# DDR3L_16bits.net
KiCad netlist of a schematic drawn in Altium Designer
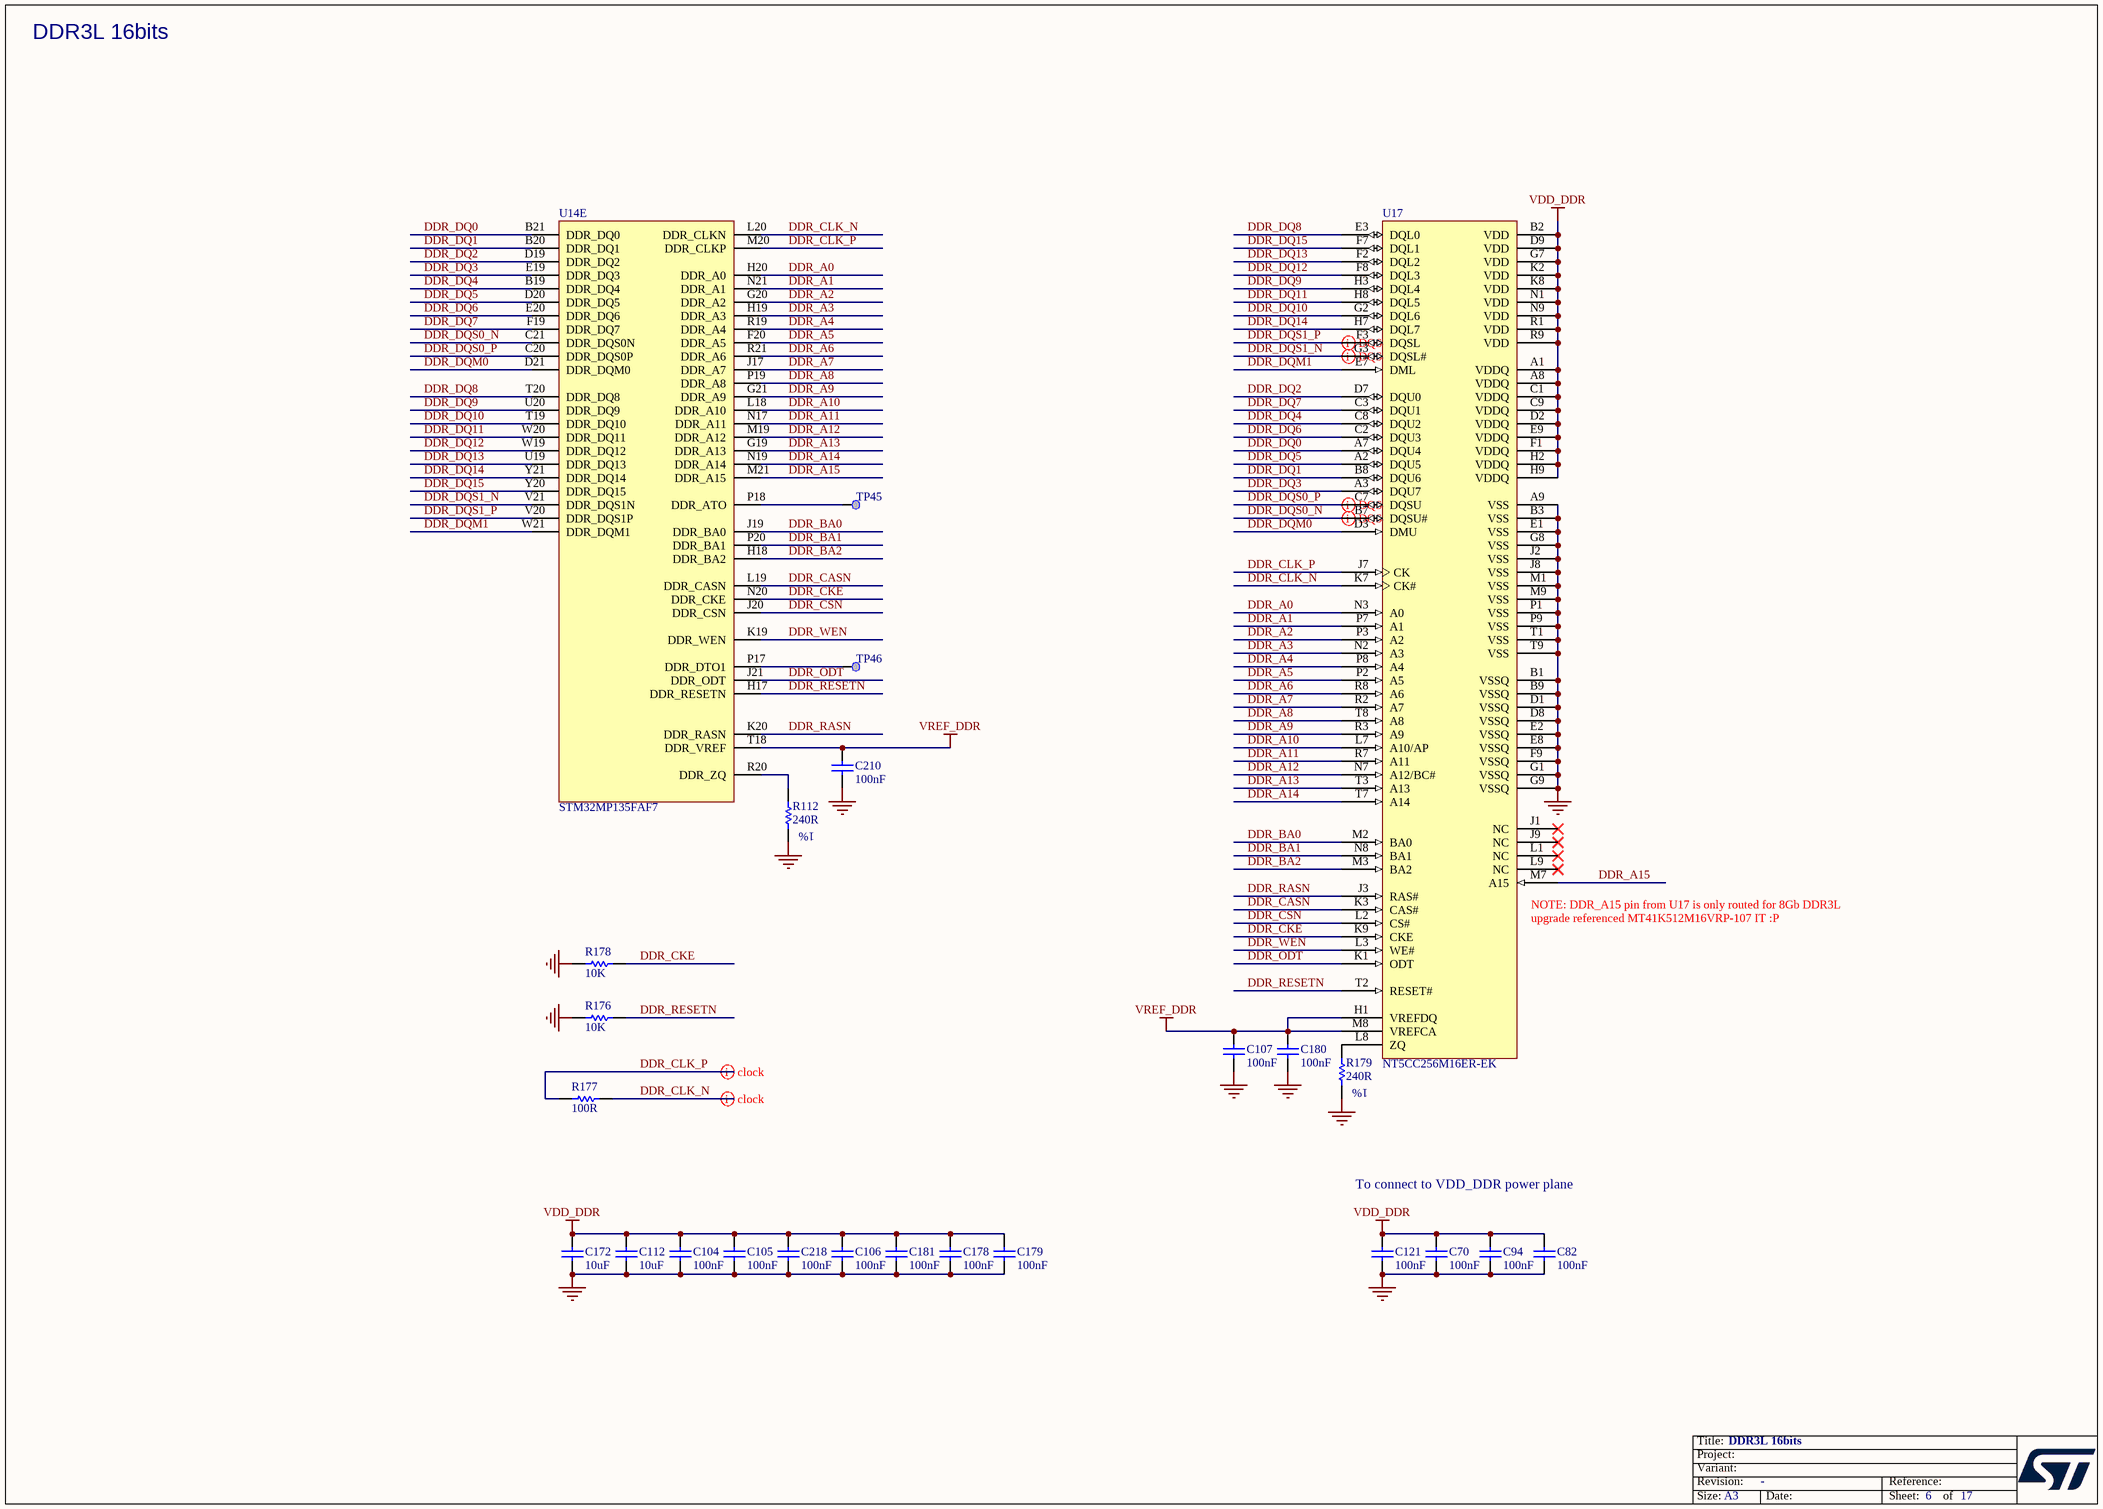
[diagram p0: DDR3L_16bits.SchDoc]

(export (version "E")
  (design (tool "Eeschema 10.0.6"))
  (components
    (comp (ref "C70")
      (value "100nF")
      (footprint "C0402")
      (description "Capacitor, MLCC, 100nF, 16V, X7R, +/-10%, 0402, T=0.5mm")
      (fields (field (name "INTERNAL_PART_NUMBER") "MCD-00006") (field (name "MANUFACTURER") "YAGEO"))
      (libsource (lib "MCD_PARTS_database") (part "Capacitor"))
    )
    (comp (ref "C82")
      (value "100nF")
      (footprint "C0402")
      (description "Capacitor, MLCC, 100nF, 16V, X7R, +/-10%, 0402, T=0.5mm")
      (fields (field (name "INTERNAL_PART_NUMBER") "MCD-00006") (field (name "MANUFACTURER") "YAGEO"))
      (libsource (lib "MCD_PARTS_database") (part "Capacitor"))
    )
    (comp (ref "C94")
      (value "100nF")
      (footprint "C0402")
      (description "Capacitor, MLCC, 100nF, 16V, X7R, +/-10%, 0402, T=0.5mm")
      (fields (field (name "INTERNAL_PART_NUMBER") "MCD-00006") (field (name "MANUFACTURER") "YAGEO"))
      (libsource (lib "MCD_PARTS_database") (part "Capacitor"))
    )
    (comp (ref "C104")
      (value "100nF")
      (footprint "C0402")
      (description "Capacitor, MLCC, 100nF, 16V, X7R, +/-10%, 0402, T=0.5mm")
      (fields (field (name "INTERNAL_PART_NUMBER") "MCD-00006") (field (name "MANUFACTURER") "YAGEO"))
      (libsource (lib "MCD_PARTS_database") (part "Capacitor"))
    )
    (comp (ref "C105")
      (value "100nF")
      (footprint "C0402")
      (description "Capacitor, MLCC, 100nF, 16V, X7R, +/-10%, 0402, T=0.5mm")
      (fields (field (name "INTERNAL_PART_NUMBER") "MCD-00006") (field (name "MANUFACTURER") "YAGEO"))
      (libsource (lib "MCD_PARTS_database") (part "Capacitor"))
    )
    (comp (ref "C106")
      (value "100nF")
      (footprint "C0402")
      (description "Capacitor, MLCC, 100nF, 16V, X7R, +/-10%, 0402, T=0.5mm")
      (fields (field (name "INTERNAL_PART_NUMBER") "MCD-00006") (field (name "MANUFACTURER") "YAGEO"))
      (libsource (lib "MCD_PARTS_database") (part "Capacitor"))
    )
    (comp (ref "C107")
      (value "100nF")
      (footprint "C0402")
      (description "Capacitor, MLCC, 100nF, 16V, X7R, +/-10%, 0402, T=0.5mm")
      (fields
        (field (name "INTERNAL_PART_NUMBER") "MCD-00006")
        (field (name "MANUFACTURER_PART_NUMBER") "CC0402KRX7R7BB104")
      )
      (libsource (lib "MCD_PARTS_database") (part "Capacitor"))
    )
    (comp (ref "C112")
      (value "10uF")
      (footprint "C0603")
      (description "Capacitor, MLCC, 10uF, 10V, X5R, +/-10%, 0603, T=0.8mm")
      (fields
        (field (name "INTERNAL_PART_NUMBER") "MCD-00099")
        (field (name "MANUFACTURER_PART_NUMBER") "GRM188R61A106KE69D")
      )
      (libsource (lib "MCD_PARTS_database") (part "Capacitor"))
    )
    (comp (ref "C121")
      (value "100nF")
      (footprint "C0402")
      (description "Capacitor, MLCC, 100nF, 16V, X7R, +/-10%, 0402, T=0.5mm")
      (fields (field (name "INTERNAL_PART_NUMBER") "MCD-00006") (field (name "MANUFACTURER") "YAGEO"))
      (libsource (lib "MCD_PARTS_database") (part "Capacitor"))
    )
    (comp (ref "C172")
      (value "10uF")
      (footprint "C0603")
      (description "Capacitor, MLCC, 10uF, 10V, X5R, +/-10%, 0603, T=0.8mm")
      (fields
        (field (name "INTERNAL_PART_NUMBER") "MCD-00099")
        (field (name "MANUFACTURER_PART_NUMBER") "GRM188R61A106KE69D")
      )
      (libsource (lib "MCD_PARTS_database") (part "Capacitor"))
    )
    (comp (ref "C178")
      (value "100nF")
      (footprint "C0402")
      (description "Capacitor, MLCC, 100nF, 16V, X7R, +/-10%, 0402, T=0.5mm")
      (fields (field (name "INTERNAL_PART_NUMBER") "MCD-00006") (field (name "MANUFACTURER") "YAGEO"))
      (libsource (lib "MCD_PARTS_database") (part "Capacitor"))
    )
    (comp (ref "C179")
      (value "100nF")
      (footprint "C0402")
      (description "Capacitor, MLCC, 100nF, 16V, X7R, +/-10%, 0402, T=0.5mm")
      (fields (field (name "INTERNAL_PART_NUMBER") "MCD-00006") (field (name "MANUFACTURER") "YAGEO"))
      (libsource (lib "MCD_PARTS_database") (part "Capacitor"))
    )
    (comp (ref "C180")
      (value "100nF")
      (footprint "C0402")
      (description "Capacitor, MLCC, 100nF, 16V, X7R, +/-10%, 0402, T=0.5mm")
      (fields
        (field (name "INTERNAL_PART_NUMBER") "MCD-00006")
        (field (name "MANUFACTURER_PART_NUMBER") "CC0402KRX7R7BB104")
      )
      (libsource (lib "MCD_PARTS_database") (part "Capacitor"))
    )
    (comp (ref "C181")
      (value "100nF")
      (footprint "C0402")
      (description "Capacitor, MLCC, 100nF, 16V, X7R, +/-10%, 0402, T=0.5mm")
      (fields (field (name "INTERNAL_PART_NUMBER") "MCD-00006") (field (name "MANUFACTURER") "YAGEO"))
      (libsource (lib "MCD_PARTS_database") (part "Capacitor"))
    )
    (comp (ref "C210")
      (value "100nF")
      (footprint "C0402")
      (description "Capacitor, MLCC, 100nF, 16V, X7R, +/-10%, 0402, T=0.5mm")
      (fields (field (name "INTERNAL_PART_NUMBER") "MCD-00006") (field (name "MANUFACTURER") "YAGEO"))
      (libsource (lib "MCD_PARTS_database") (part "Capacitor"))
    )
    (comp (ref "C218")
      (value "100nF")
      (footprint "C0402")
      (description "Capacitor, MLCC, 100nF, 16V, X7R, +/-10%, 0402, T=0.5mm")
      (fields (field (name "INTERNAL_PART_NUMBER") "MCD-00006") (field (name "MANUFACTURER") "YAGEO"))
      (libsource (lib "MCD_PARTS_database") (part "Capacitor"))
    )
    (comp (ref "R112")
      (value "240R")
      (footprint "R0402")
      (description "Resistor, 240R, 0402, +/-1%, 1/16W")
      (fields (field (name "INTERNAL_PART_NUMBER") "MCD-00120") (field (name "MANUFACTURER") "YAGEO"))
      (libsource (lib "MCD_PARTS_database") (part "Resistor"))
    )
    (comp (ref "R176")
      (value "10K")
      (footprint "R0402")
      (description "Resistor, 10K, 0402, +/-1%, 1/16W")
      (fields
        (field (name "INTERNAL_PART_NUMBER") "MCD-00053")
        (field (name "MANUFACTURER_PART_NUMBER") "RC0402FR-0710KL")
      )
      (libsource (lib "MCD_PARTS_database") (part "Resistor"))
    )
    (comp (ref "R177")
      (value "100R")
      (footprint "R0402")
      (description "Resistor, 100R, 0402, +/- 1%, 1/16W")
      (fields
        (field (name "INTERNAL_PART_NUMBER") "MCD-00067")
        (field (name "MANUFACTURER_PART_NUMBER") "RC0402FR-07100RL")
      )
      (libsource (lib "MCD_PARTS_database") (part "Resistor"))
    )
    (comp (ref "R178")
      (value "10K")
      (footprint "R0402")
      (description "Resistor, 10K, 0402, +/-1%, 1/16W")
      (fields
        (field (name "INTERNAL_PART_NUMBER") "MCD-00053")
        (field (name "MANUFACTURER_PART_NUMBER") "RC0402FR-0710KL")
      )
      (libsource (lib "MCD_PARTS_database") (part "Resistor"))
    )
    (comp (ref "R179")
      (value "240R")
      (footprint "R0402")
      (description "Resistor, 240R, 0402, +/-1%, 1/16W")
      (fields
        (field (name "INTERNAL_PART_NUMBER") "MCD-00120")
        (field (name "MANUFACTURER_PART_NUMBER") "RC0402FR-07240RL")
      )
      (libsource (lib "MCD_PARTS_database") (part "Resistor"))
    )
    (comp (ref "TP45")
      (value "Test Point")
      (footprint "TP_SMD_1MM")
      (description "Test Point 1mm")
      (fields (field (name "INTERNAL_PART_NUMBER") "MCD-00074"))
      (libsource (lib "MCD_PARTS_database") (part "Test Point"))
    )
    (comp (ref "TP46")
      (value "Test Point")
      (footprint "TP_SMD_1MM")
      (description "Test Point 1mm")
      (fields (field (name "INTERNAL_PART_NUMBER") "MCD-00074"))
      (libsource (lib "MCD_PARTS_database") (part "Test Point"))
    )
    (comp (ref "U14")
      (value "STM32MP135FAF7")
      (footprint "ICC_TFBGA320_11X11_STM32MP135FA7_P050_H1P20")
      (fields
        (field (name "INTERNAL_PART_NUMBER") "MCD-02251")
        (field (name "MANUFACTURER") "STMICROELECTRONICS")
      )
      (libsource (lib "MCD_PARTS_database") (part "STM32MP135FAF7"))
    )
    (comp (ref "U17")
      (value "NT5CC256M16ER-EK")
      (footprint "ICC_VFBGA96_9x13_P080")
      (description "Memory,DDR3L,4Gb,256Mbx16,933Mhz,1V35,TFBGA")
      (fields (field (name "INTERNAL_PART_NUMBER") "MCD-01811") (field (name "MANUFACTURER") "NANYA"))
      (libsource (lib "MCD_PARTS_database") (part "NT5CC256M16ER-EK"))
    )
  )
  (nets
    (net (code "1") (name "/DDR_A0") (class "Default")
      (node (ref "U14") (pin "H20") (pinfunction "DDR_A0_H20") (pintype "passive"))
      (node (ref "U17") (pin "N3") (pinfunction "A0_N3") (pintype "input"))
    )
    (net (code "2") (name "/DDR_A1") (class "Default")
      (node (ref "U14") (pin "N21") (pinfunction "DDR_A1_N21") (pintype "passive"))
      (node (ref "U17") (pin "P7") (pinfunction "A1_P7") (pintype "input"))
    )
    (net (code "3") (name "/DDR_A2") (class "Default")
      (node (ref "U14") (pin "G20") (pinfunction "DDR_A2_G20") (pintype "passive"))
      (node (ref "U17") (pin "P3") (pinfunction "A2_P3") (pintype "input"))
    )
    (net (code "4") (name "/DDR_A3") (class "Default")
      (node (ref "U14") (pin "H19") (pinfunction "DDR_A3_H19") (pintype "passive"))
      (node (ref "U17") (pin "N2") (pinfunction "A3_N2") (pintype "input"))
    )
    (net (code "5") (name "/DDR_A4") (class "Default")
      (node (ref "U14") (pin "R19") (pinfunction "DDR_A4_R19") (pintype "passive"))
      (node (ref "U17") (pin "P8") (pinfunction "A4_P8") (pintype "input"))
    )
    (net (code "6") (name "/DDR_A5") (class "Default")
      (node (ref "U14") (pin "F20") (pinfunction "DDR_A5_F20") (pintype "passive"))
      (node (ref "U17") (pin "P2") (pinfunction "A5_P2") (pintype "input"))
    )
    (net (code "7") (name "/DDR_A6") (class "Default")
      (node (ref "U14") (pin "R21") (pinfunction "DDR_A6_R21") (pintype "passive"))
      (node (ref "U17") (pin "R8") (pinfunction "A6_R8") (pintype "input"))
    )
    (net (code "8") (name "/DDR_A7") (class "Default")
      (node (ref "U14") (pin "J17") (pinfunction "DDR_A7_J17") (pintype "passive"))
      (node (ref "U17") (pin "R2") (pinfunction "A7_R2") (pintype "input"))
    )
    (net (code "9") (name "/DDR_A8") (class "Default")
      (node (ref "U14") (pin "P19") (pinfunction "DDR_A8_P19") (pintype "passive"))
      (node (ref "U17") (pin "T8") (pinfunction "A8_T8") (pintype "input"))
    )
    (net (code "10") (name "/DDR_A9") (class "Default")
      (node (ref "U14") (pin "G21") (pinfunction "DDR_A9_G21") (pintype "passive"))
      (node (ref "U17") (pin "R3") (pinfunction "A9_R3") (pintype "input"))
    )
    (net (code "11") (name "/DDR_A10") (class "Default")
      (node (ref "U14") (pin "L18") (pinfunction "DDR_A10_L18") (pintype "passive"))
      (node (ref "U17") (pin "L7") (pinfunction "A10/AP_L7") (pintype "input"))
    )
    (net (code "12") (name "/DDR_A11") (class "Default")
      (node (ref "U14") (pin "N17") (pinfunction "DDR_A11_N17") (pintype "passive"))
      (node (ref "U17") (pin "R7") (pinfunction "A11_R7") (pintype "input"))
    )
    (net (code "13") (name "/DDR_A12") (class "Default")
      (node (ref "U14") (pin "M19") (pinfunction "DDR_A12_M19") (pintype "passive"))
      (node (ref "U17") (pin "N7") (pinfunction "A12/BC#_N7") (pintype "input"))
    )
    (net (code "14") (name "/DDR_A13") (class "Default")
      (node (ref "U14") (pin "G19") (pinfunction "DDR_A13_G19") (pintype "passive"))
      (node (ref "U17") (pin "T3") (pinfunction "A13_T3") (pintype "input"))
    )
    (net (code "15") (name "/DDR_A14") (class "Default")
      (node (ref "U14") (pin "N19") (pinfunction "DDR_A14_N19") (pintype "passive"))
      (node (ref "U17") (pin "T7") (pinfunction "A14_T7") (pintype "input"))
    )
    (net (code "16") (name "/DDR_A15") (class "Default")
      (node (ref "U14") (pin "M21") (pinfunction "DDR_A15_M21") (pintype "passive"))
      (node (ref "U17") (pin "M7") (pinfunction "A15_M7") (pintype "input"))
    )
    (net (code "17") (name "/DDR_BA0") (class "Default")
      (node (ref "U14") (pin "J19") (pinfunction "DDR_BA0_J19") (pintype "passive"))
      (node (ref "U17") (pin "M2") (pinfunction "BA0_M2") (pintype "input"))
    )
    (net (code "18") (name "/DDR_BA1") (class "Default")
      (node (ref "U14") (pin "P20") (pinfunction "DDR_BA1_P20") (pintype "passive"))
      (node (ref "U17") (pin "N8") (pinfunction "BA1_N8") (pintype "input"))
    )
    (net (code "19") (name "/DDR_BA2") (class "Default")
      (node (ref "U14") (pin "H18") (pinfunction "DDR_BA2_H18") (pintype "passive"))
      (node (ref "U17") (pin "M3") (pinfunction "BA2_M3") (pintype "input"))
    )
    (net (code "20") (name "/DDR_CASN") (class "Default")
      (node (ref "U14") (pin "L19") (pinfunction "DDR_CASN_L19") (pintype "passive"))
      (node (ref "U17") (pin "K3") (pinfunction "CAS#_K3") (pintype "input"))
    )
    (net (code "21") (name "/DDR_CKE") (class "Default")
      (node (ref "R178") (pin "2") (pinfunction "2_2") (pintype "passive"))
      (node (ref "U14") (pin "N20") (pinfunction "DDR_CKE_N20") (pintype "passive"))
      (node (ref "U17") (pin "K9") (pinfunction "CKE_K9") (pintype "input"))
    )
    (net (code "22") (name "/DDR_CLK_N") (class "Default")
      (node (ref "R177") (pin "2") (pinfunction "2_2") (pintype "passive"))
      (node (ref "U14") (pin "L20") (pinfunction "DDR_CLKN_L20") (pintype "passive"))
      (node (ref "U17") (pin "K7") (pinfunction "CK#_K7") (pintype "input"))
    )
    (net (code "23") (name "/DDR_CLK_P") (class "Default")
      (node (ref "R177") (pin "1") (pinfunction "1_1") (pintype "passive"))
      (node (ref "U14") (pin "M20") (pinfunction "DDR_CLKP_M20") (pintype "passive"))
      (node (ref "U17") (pin "J7") (pinfunction "CK_J7") (pintype "input"))
    )
    (net (code "24") (name "/DDR_CSN") (class "Default")
      (node (ref "U14") (pin "J20") (pinfunction "DDR_CSN_J20") (pintype "passive"))
      (node (ref "U17") (pin "L2") (pinfunction "CS#_L2") (pintype "input"))
    )
    (net (code "25") (name "/DDR_DQ0") (class "Default")
      (node (ref "U14") (pin "B21") (pinfunction "DDR_DQ0_B21") (pintype "passive"))
      (node (ref "U17") (pin "A7") (pinfunction "DQU4_A7") (pintype "bidirectional"))
    )
    (net (code "26") (name "/DDR_DQ1") (class "Default")
      (node (ref "U14") (pin "B20") (pinfunction "DDR_DQ1_B20") (pintype "passive"))
      (node (ref "U17") (pin "B8") (pinfunction "DQU6_B8") (pintype "bidirectional"))
    )
    (net (code "27") (name "/DDR_DQ2") (class "Default")
      (node (ref "U14") (pin "D19") (pinfunction "DDR_DQ2_D19") (pintype "passive"))
      (node (ref "U17") (pin "D7") (pinfunction "DQU0_D7") (pintype "bidirectional"))
    )
    (net (code "28") (name "/DDR_DQ3") (class "Default")
      (node (ref "U14") (pin "E19") (pinfunction "DDR_DQ3_E19") (pintype "passive"))
      (node (ref "U17") (pin "A3") (pinfunction "DQU7_A3") (pintype "bidirectional"))
    )
    (net (code "29") (name "/DDR_DQ4") (class "Default")
      (node (ref "U14") (pin "B19") (pinfunction "DDR_DQ4_B19") (pintype "passive"))
      (node (ref "U17") (pin "C8") (pinfunction "DQU2_C8") (pintype "bidirectional"))
    )
    (net (code "30") (name "/DDR_DQ5") (class "Default")
      (node (ref "U14") (pin "D20") (pinfunction "DDR_DQ5_D20") (pintype "passive"))
      (node (ref "U17") (pin "A2") (pinfunction "DQU5_A2") (pintype "bidirectional"))
    )
    (net (code "31") (name "/DDR_DQ6") (class "Default")
      (node (ref "U14") (pin "E20") (pinfunction "DDR_DQ6_E20") (pintype "passive"))
      (node (ref "U17") (pin "C2") (pinfunction "DQU3_C2") (pintype "bidirectional"))
    )
    (net (code "32") (name "/DDR_DQ7") (class "Default")
      (node (ref "U14") (pin "F19") (pinfunction "DDR_DQ7_F19") (pintype "passive"))
      (node (ref "U17") (pin "C3") (pinfunction "DQU1_C3") (pintype "bidirectional"))
    )
    (net (code "33") (name "/DDR_DQ8") (class "Default")
      (node (ref "U14") (pin "T20") (pinfunction "DDR_DQ8_T20") (pintype "passive"))
      (node (ref "U17") (pin "E3") (pinfunction "DQL0_E3") (pintype "bidirectional"))
    )
    (net (code "34") (name "/DDR_DQ9") (class "Default")
      (node (ref "U14") (pin "U20") (pinfunction "DDR_DQ9_U20") (pintype "passive"))
      (node (ref "U17") (pin "H3") (pinfunction "DQL4_H3") (pintype "bidirectional"))
    )
    (net (code "35") (name "/DDR_DQ10") (class "Default")
      (node (ref "U14") (pin "T19") (pinfunction "DDR_DQ10_T19") (pintype "passive"))
      (node (ref "U17") (pin "G2") (pinfunction "DQL6_G2") (pintype "bidirectional"))
    )
    (net (code "36") (name "/DDR_DQ11") (class "Default")
      (node (ref "U14") (pin "W20") (pinfunction "DDR_DQ11_W20") (pintype "passive"))
      (node (ref "U17") (pin "H8") (pinfunction "DQL5_H8") (pintype "bidirectional"))
    )
    (net (code "37") (name "/DDR_DQ12") (class "Default")
      (node (ref "U14") (pin "W19") (pinfunction "DDR_DQ12_W19") (pintype "passive"))
      (node (ref "U17") (pin "F8") (pinfunction "DQL3_F8") (pintype "bidirectional"))
    )
    (net (code "38") (name "/DDR_DQ13") (class "Default")
      (node (ref "U14") (pin "U19") (pinfunction "DDR_DQ13_U19") (pintype "passive"))
      (node (ref "U17") (pin "F2") (pinfunction "DQL2_F2") (pintype "bidirectional"))
    )
    (net (code "39") (name "/DDR_DQ14") (class "Default")
      (node (ref "U14") (pin "Y21") (pinfunction "DDR_DQ14_Y21") (pintype "passive"))
      (node (ref "U17") (pin "H7") (pinfunction "DQL7_H7") (pintype "bidirectional"))
    )
    (net (code "40") (name "/DDR_DQ15") (class "Default")
      (node (ref "U14") (pin "Y20") (pinfunction "DDR_DQ15_Y20") (pintype "passive"))
      (node (ref "U17") (pin "F7") (pinfunction "DQL1_F7") (pintype "bidirectional"))
    )
    (net (code "41") (name "/DDR_DQM0") (class "Default")
      (node (ref "U14") (pin "D21") (pinfunction "DDR_DQM0_D21") (pintype "passive"))
      (node (ref "U17") (pin "D3") (pinfunction "DMU_D3") (pintype "input"))
    )
    (net (code "42") (name "/DDR_DQM1") (class "Default")
      (node (ref "U14") (pin "W21") (pinfunction "DDR_DQM1_W21") (pintype "passive"))
      (node (ref "U17") (pin "E7") (pinfunction "DML_E7") (pintype "input"))
    )
    (net (code "43") (name "/DDR_DQS0_N") (class "Default")
      (node (ref "U14") (pin "C21") (pinfunction "DDR_DQS0N_C21") (pintype "passive"))
      (node (ref "U17") (pin "B7") (pinfunction "DQSU#_B7") (pintype "bidirectional"))
    )
    (net (code "44") (name "/DDR_DQS0_P") (class "Default")
      (node (ref "U14") (pin "C20") (pinfunction "DDR_DQS0P_C20") (pintype "passive"))
      (node (ref "U17") (pin "C7") (pinfunction "DQSU_C7") (pintype "bidirectional"))
    )
    (net (code "45") (name "/DDR_DQS1_N") (class "Default")
      (node (ref "U14") (pin "V21") (pinfunction "DDR_DQS1N_V21") (pintype "passive"))
      (node (ref "U17") (pin "G3") (pinfunction "DQSL#_G3") (pintype "bidirectional"))
    )
    (net (code "46") (name "/DDR_DQS1_P") (class "Default")
      (node (ref "U14") (pin "V20") (pinfunction "DDR_DQS1P_V20") (pintype "passive"))
      (node (ref "U17") (pin "F3") (pinfunction "DQSL_F3") (pintype "bidirectional"))
    )
    (net (code "47") (name "/DDR_ODT") (class "Default")
      (node (ref "U14") (pin "J21") (pinfunction "DDR_ODT_J21") (pintype "passive"))
      (node (ref "U17") (pin "K1") (pinfunction "ODT_K1") (pintype "input"))
    )
    (net (code "48") (name "/DDR_RASN") (class "Default")
      (node (ref "U14") (pin "K20") (pinfunction "DDR_RASN_K20") (pintype "passive"))
      (node (ref "U17") (pin "J3") (pinfunction "RAS#_J3") (pintype "input"))
    )
    (net (code "49") (name "/DDR_RESETN") (class "Default")
      (node (ref "R176") (pin "2") (pinfunction "2_2") (pintype "passive"))
      (node (ref "U14") (pin "H17") (pinfunction "DDR_RESETN_H17") (pintype "passive"))
      (node (ref "U17") (pin "T2") (pinfunction "RESET#_T2") (pintype "input"))
    )
    (net (code "50") (name "/DDR_WEN") (class "Default")
      (node (ref "U14") (pin "K19") (pinfunction "DDR_WEN_K19") (pintype "passive"))
      (node (ref "U17") (pin "L3") (pinfunction "WE#_L3") (pintype "input"))
    )
    (net (code "51") (name "GND") (class "Default")
      (node (ref "C104") (pin "1") (pinfunction "1_1") (pintype "passive"))
      (node (ref "C105") (pin "1") (pinfunction "1_1") (pintype "passive"))
      (node (ref "C106") (pin "1") (pinfunction "1_1") (pintype "passive"))
      (node (ref "C107") (pin "2") (pinfunction "2_2") (pintype "passive"))
      (node (ref "C112") (pin "1") (pinfunction "1_1") (pintype "passive"))
      (node (ref "C121") (pin "1") (pinfunction "1_1") (pintype "passive"))
      (node (ref "C172") (pin "1") (pinfunction "1_1") (pintype "passive"))
      (node (ref "C178") (pin "1") (pinfunction "1_1") (pintype "passive"))
      (node (ref "C179") (pin "1") (pinfunction "1_1") (pintype "passive"))
      (node (ref "C180") (pin "2") (pinfunction "2_2") (pintype "passive"))
      (node (ref "C181") (pin "1") (pinfunction "1_1") (pintype "passive"))
      (node (ref "C210") (pin "2") (pinfunction "2_2") (pintype "passive"))
      (node (ref "C218") (pin "1") (pinfunction "1_1") (pintype "passive"))
      (node (ref "C70") (pin "1") (pinfunction "1_1") (pintype "passive"))
      (node (ref "C82") (pin "1") (pinfunction "1_1") (pintype "passive"))
      (node (ref "C94") (pin "1") (pinfunction "1_1") (pintype "passive"))
      (node (ref "R112") (pin "1") (pinfunction "1_1") (pintype "passive"))
      (node (ref "R176") (pin "1") (pinfunction "1_1") (pintype "passive"))
      (node (ref "R178") (pin "1") (pinfunction "1_1") (pintype "passive"))
      (node (ref "R179") (pin "1") (pinfunction "1_1") (pintype "passive"))
      (node (ref "U17") (pin "A9") (pinfunction "VSS_A9") (pintype "power_in"))
      (node (ref "U17") (pin "B1") (pinfunction "VSSQ_B1") (pintype "power_in"))
      (node (ref "U17") (pin "B3") (pinfunction "VSS_B3") (pintype "power_in"))
      (node (ref "U17") (pin "B9") (pinfunction "VSSQ_B9") (pintype "power_in"))
      (node (ref "U17") (pin "D1") (pinfunction "VSSQ_D1") (pintype "power_in"))
      (node (ref "U17") (pin "D8") (pinfunction "VSSQ_D8") (pintype "power_in"))
      (node (ref "U17") (pin "E1") (pinfunction "VSS_E1") (pintype "power_in"))
      (node (ref "U17") (pin "E2") (pinfunction "VSSQ_E2") (pintype "power_in"))
      (node (ref "U17") (pin "E8") (pinfunction "VSSQ_E8") (pintype "power_in"))
      (node (ref "U17") (pin "F9") (pinfunction "VSSQ_F9") (pintype "power_in"))
      (node (ref "U17") (pin "G1") (pinfunction "VSSQ_G1") (pintype "power_in"))
      (node (ref "U17") (pin "G8") (pinfunction "VSS_G8") (pintype "power_in"))
      (node (ref "U17") (pin "G9") (pinfunction "VSSQ_G9") (pintype "power_in"))
      (node (ref "U17") (pin "J2") (pinfunction "VSS_J2") (pintype "power_in"))
      (node (ref "U17") (pin "J8") (pinfunction "VSS_J8") (pintype "power_in"))
      (node (ref "U17") (pin "M1") (pinfunction "VSS_M1") (pintype "power_in"))
      (node (ref "U17") (pin "M9") (pinfunction "VSS_M9") (pintype "power_in"))
      (node (ref "U17") (pin "P1") (pinfunction "VSS_P1") (pintype "power_in"))
      (node (ref "U17") (pin "P9") (pinfunction "VSS_P9") (pintype "power_in"))
      (node (ref "U17") (pin "T1") (pinfunction "VSS_T1") (pintype "power_in"))
      (node (ref "U17") (pin "T9") (pinfunction "VSS_T9") (pintype "power_in"))
    )
    (net (code "52") (name "Net-(U14E-DDR_ATO)") (class "Default")
      (node (ref "TP45") (pin "1") (pinfunction "1_1") (pintype "passive"))
      (node (ref "U14") (pin "P18") (pinfunction "DDR_ATO_P18") (pintype "passive"))
    )
    (net (code "53") (name "Net-(U14E-DDR_DTO1)") (class "Default")
      (node (ref "TP46") (pin "1") (pinfunction "1_1") (pintype "passive"))
      (node (ref "U14") (pin "P17") (pinfunction "DDR_DTO1_P17") (pintype "passive"))
    )
    (net (code "54") (name "Net-(U14E-DDR_ZQ)") (class "Default")
      (node (ref "R112") (pin "2") (pinfunction "2_2") (pintype "passive"))
      (node (ref "U14") (pin "R20") (pinfunction "DDR_ZQ_R20") (pintype "passive"))
    )
    (net (code "55") (name "Net-(U17-ZQ)") (class "Default")
      (node (ref "R179") (pin "2") (pinfunction "2_2") (pintype "passive"))
      (node (ref "U17") (pin "L8") (pinfunction "ZQ_L8") (pintype "passive"))
    )
    (net (code "56") (name "VDD_DDR") (class "Default")
      (node (ref "C104") (pin "2") (pinfunction "2_2") (pintype "passive"))
      (node (ref "C105") (pin "2") (pinfunction "2_2") (pintype "passive"))
      (node (ref "C106") (pin "2") (pinfunction "2_2") (pintype "passive"))
      (node (ref "C112") (pin "2") (pinfunction "2_2") (pintype "passive"))
      (node (ref "C121") (pin "2") (pinfunction "2_2") (pintype "passive"))
      (node (ref "C172") (pin "2") (pinfunction "2_2") (pintype "passive"))
      (node (ref "C178") (pin "2") (pinfunction "2_2") (pintype "passive"))
      (node (ref "C179") (pin "2") (pinfunction "2_2") (pintype "passive"))
      (node (ref "C181") (pin "2") (pinfunction "2_2") (pintype "passive"))
      (node (ref "C218") (pin "2") (pinfunction "2_2") (pintype "passive"))
      (node (ref "C70") (pin "2") (pinfunction "2_2") (pintype "passive"))
      (node (ref "C82") (pin "2") (pinfunction "2_2") (pintype "passive"))
      (node (ref "C94") (pin "2") (pinfunction "2_2") (pintype "passive"))
      (node (ref "U17") (pin "A1") (pinfunction "VDDQ_A1") (pintype "power_in"))
      (node (ref "U17") (pin "A8") (pinfunction "VDDQ_A8") (pintype "power_in"))
      (node (ref "U17") (pin "B2") (pinfunction "VDD_B2") (pintype "power_in"))
      (node (ref "U17") (pin "C1") (pinfunction "VDDQ_C1") (pintype "power_in"))
      (node (ref "U17") (pin "C9") (pinfunction "VDDQ_C9") (pintype "power_in"))
      (node (ref "U17") (pin "D2") (pinfunction "VDDQ_D2") (pintype "power_in"))
      (node (ref "U17") (pin "D9") (pinfunction "VDD_D9") (pintype "power_in"))
      (node (ref "U17") (pin "E9") (pinfunction "VDDQ_E9") (pintype "power_in"))
      (node (ref "U17") (pin "F1") (pinfunction "VDDQ_F1") (pintype "power_in"))
      (node (ref "U17") (pin "G7") (pinfunction "VDD_G7") (pintype "power_in"))
      (node (ref "U17") (pin "H2") (pinfunction "VDDQ_H2") (pintype "power_in"))
      (node (ref "U17") (pin "H9") (pinfunction "VDDQ_H9") (pintype "power_in"))
      (node (ref "U17") (pin "K2") (pinfunction "VDD_K2") (pintype "power_in"))
      (node (ref "U17") (pin "K8") (pinfunction "VDD_K8") (pintype "power_in"))
      (node (ref "U17") (pin "N1") (pinfunction "VDD_N1") (pintype "power_in"))
      (node (ref "U17") (pin "N9") (pinfunction "VDD_N9") (pintype "power_in"))
      (node (ref "U17") (pin "R1") (pinfunction "VDD_R1") (pintype "power_in"))
      (node (ref "U17") (pin "R9") (pinfunction "VDD_R9") (pintype "power_in"))
    )
    (net (code "57") (name "VREF_DDR") (class "Default")
      (node (ref "C107") (pin "1") (pinfunction "1_1") (pintype "passive"))
      (node (ref "C180") (pin "1") (pinfunction "1_1") (pintype "passive"))
      (node (ref "C210") (pin "1") (pinfunction "1_1") (pintype "passive"))
      (node (ref "U14") (pin "T18") (pinfunction "DDR_VREF_T18") (pintype "passive"))
      (node (ref "U17") (pin "H1") (pinfunction "VREFDQ_H1") (pintype "passive"))
      (node (ref "U17") (pin "M8") (pinfunction "VREFCA_M8") (pintype "passive"))
    )
    (net (code "58") (name "unconnected-(U17-NC-PadJ1)") (class "Default")
      (node (ref "U17") (pin "J1") (pinfunction "NC_J1") (pintype "passive+no_connect"))
    )
    (net (code "59") (name "unconnected-(U17-NC-PadJ9)") (class "Default")
      (node (ref "U17") (pin "J9") (pinfunction "NC_J9") (pintype "passive+no_connect"))
    )
    (net (code "60") (name "unconnected-(U17-NC-PadL1)") (class "Default")
      (node (ref "U17") (pin "L1") (pinfunction "NC_L1") (pintype "passive+no_connect"))
    )
    (net (code "61") (name "unconnected-(U17-NC-PadL9)") (class "Default")
      (node (ref "U17") (pin "L9") (pinfunction "NC_L9") (pintype "passive+no_connect"))
    )
  )
)
